# untitled.net
KiCad netlist of a schematic drawn in EAGLE
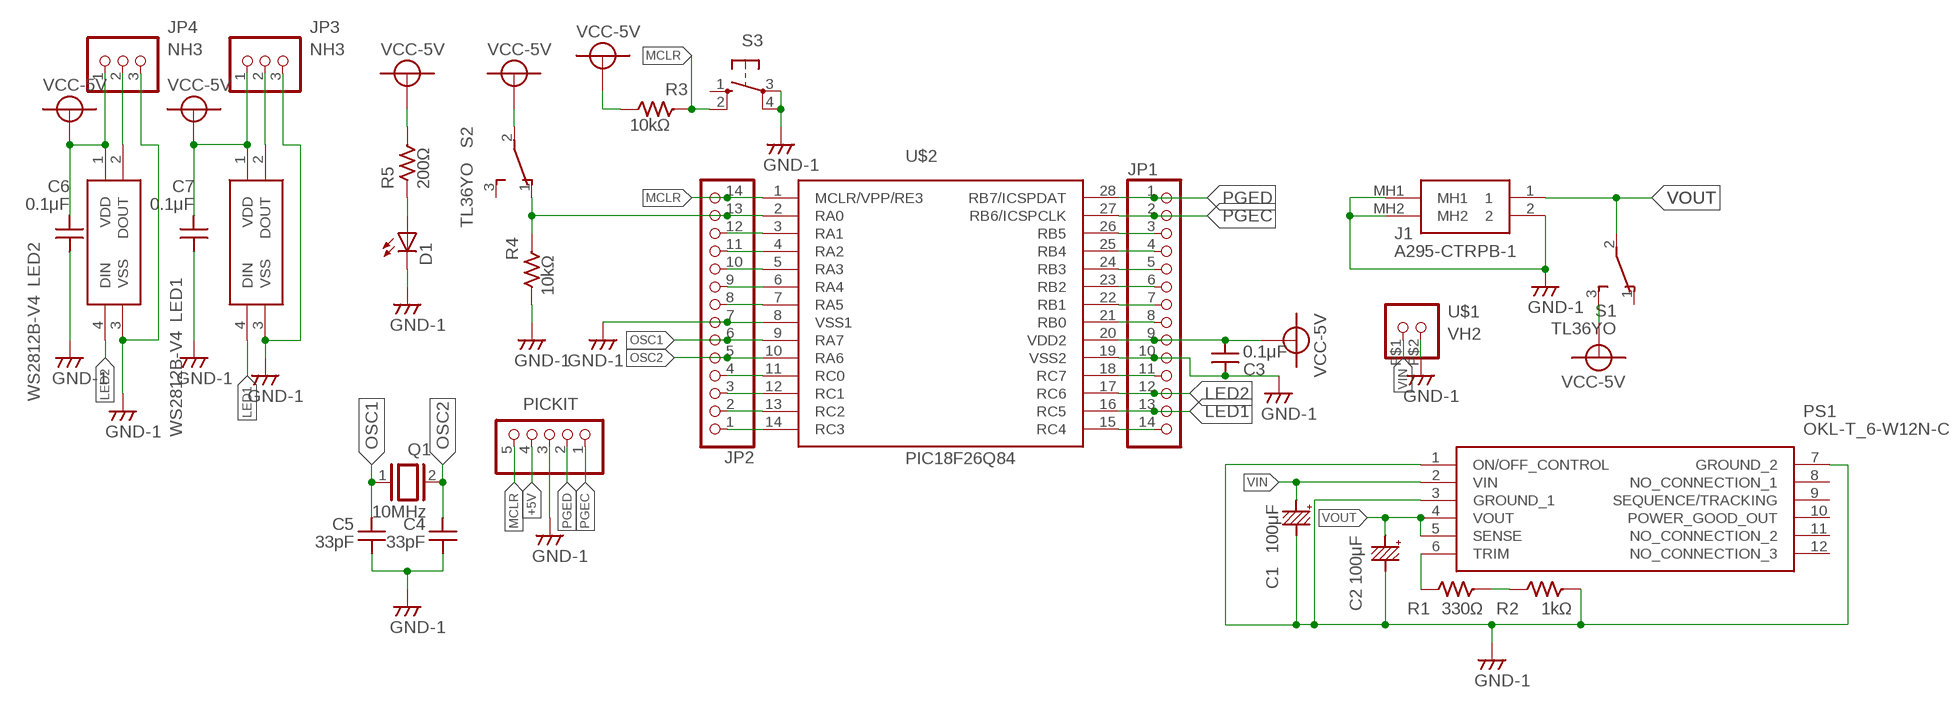
[diagram p0: schematic, sheet 1]

(export (version "E")
  (design (tool "Eeschema 10.0.6"))
  (components
    (comp (ref "C1")
      (value "100μF")
      (footprint "eagle-import:CC_3")
      (libsource (lib "eagle-import") (part "C+25V100"))
    )
    (comp (ref "C2")
      (value "100μF")
      (footprint "eagle-import:CC_3")
      (libsource (lib "eagle-import") (part "C+25V100"))
    )
    (comp (ref "C3")
      (value "0.1μF")
      (footprint "eagle-import:C_1")
      (libsource (lib "eagle-import") (part "CC2.54"))
    )
    (comp (ref "C4")
      (value "33pF")
      (footprint "eagle-import:C_1")
      (libsource (lib "eagle-import") (part "CC2.54"))
    )
    (comp (ref "C5")
      (value "33pF")
      (footprint "eagle-import:C_1")
      (libsource (lib "eagle-import") (part "CC2.54"))
    )
    (comp (ref "C6")
      (value "0.1μF")
      (footprint "eagle-import:C1608")
      (libsource (lib "eagle-import") (part "CC1068"))
    )
    (comp (ref "C7")
      (value "0.1μF")
      (footprint "eagle-import:C1608")
      (libsource (lib "eagle-import") (part "CC1068"))
    )
    (comp (ref "D1")
      (value "LED\"\"\"\"")
      (footprint "eagle-import:CHIPLED_0603")
      (libsource (lib "eagle-import") (part "LED{dblquote}{dblquote}{dblquote}{dblquote}"))
    )
    (comp (ref "J1")
      (value "A295-CTRPB-1")
      (footprint "eagle-import:A295CTRPB1")
      (libsource (lib "eagle-import") (part "A295-CTRPB-1"))
    )
    (comp (ref "JP1")
      (value "PINHD-1X14")
      (footprint "eagle-import:1X14")
      (libsource (lib "eagle-import") (part "PINHD-1X14"))
    )
    (comp (ref "JP2")
      (value "PINHD-1X14")
      (footprint "eagle-import:1X14")
      (libsource (lib "eagle-import") (part "PINHD-1X14"))
    )
    (comp (ref "JP3")
      (value "NH3")
      (footprint "eagle-import:NH3")
      (libsource (lib "eagle-import") (part "NH3"))
    )
    (comp (ref "JP4")
      (value "NH3")
      (footprint "eagle-import:NH3")
      (libsource (lib "eagle-import") (part "NH3"))
    )
    (comp (ref "LED1")
      (value "WS2812B-V4")
      (footprint "eagle-import:WS2812BV4")
      (libsource (lib "eagle-import") (part "WS2812B-V4"))
    )
    (comp (ref "LED2")
      (value "WS2812B-V4")
      (footprint "eagle-import:WS2812BV4")
      (libsource (lib "eagle-import") (part "WS2812B-V4"))
    )
    (comp (ref "PICKIT")
      (value "PINHD-1X5/90")
      (footprint "eagle-import:1X05_90")
      (libsource (lib "eagle-import") (part "PINHD-1X5/90"))
    )
    (comp (ref "PS1")
      (value "OKL-T_6-W12N-C")
      (footprint "eagle-import:OKLT6W12NC")
      (fields
        (field (name "ARROW_PART_NUMBER") "OKL-T/6-W12N-C")
        (field (name "MOUSER_PART_NUMBER") "580-OKL-T/6-W12N-C")
      )
      (libsource (lib "eagle-import") (part "OKL-T_6-W12N-C"))
    )
    (comp (ref "Q1")
      (value "10MHz")
      (footprint "eagle-import:QS")
      (libsource (lib "eagle-import") (part "XTAL/S"))
    )
    (comp (ref "R1")
      (value "330Ω")
      (footprint "eagle-import:C3216")
      (libsource (lib "eagle-import") (part "R3216(1206)"))
    )
    (comp (ref "R2")
      (value "1kΩ")
      (footprint "eagle-import:2012")
      (libsource (lib "eagle-import") (part "R2012"))
    )
    (comp (ref "R3")
      (value "10kΩ")
      (footprint "eagle-import:2012")
      (libsource (lib "eagle-import") (part "R2012"))
    )
    (comp (ref "R4")
      (value "10kΩ")
      (footprint "eagle-import:2012")
      (libsource (lib "eagle-import") (part "R2012"))
    )
    (comp (ref "R5")
      (value "200Ω")
      (footprint "eagle-import:C3216")
      (libsource (lib "eagle-import") (part "R3216(1206)"))
    )
    (comp (ref "S1")
      (value "TL36YO")
      (footprint "eagle-import:TL3XYO")
      (libsource (lib "eagle-import") (part "TL36YO"))
    )
    (comp (ref "S2")
      (value "TL36YO")
      (footprint "eagle-import:TL3XYO")
      (libsource (lib "eagle-import") (part "TL36YO"))
    )
    (comp (ref "S3")
      (value "10-XX")
      (footprint "eagle-import:B3F-10XX")
      (fields (field (name "MPN") "B3F-1000"))
      (libsource (lib "eagle-import") (part "10-XX"))
    )
    (comp (ref "U$1")
      (value "VH2")
      (footprint "eagle-import:VH2")
      (libsource (lib "eagle-import") (part "VH2"))
    )
    (comp (ref "U$2")
      (value "PIC18F26Q84")
      (footprint "eagle-import:DIL28-3")
      (libsource (lib "eagle-import") (part "PIC18F26Q84"))
    )
  )
  (nets
    (net (code "1") (name "+5V") (class "Default")
      (node (ref "C3") (pin "P$1") (pinfunction "P$1_P$1") (pintype "passive"))
      (node (ref "C6") (pin "2") (pinfunction "P$2_2") (pintype "passive"))
      (node (ref "C7") (pin "2") (pinfunction "P$2_2") (pintype "passive"))
      (node (ref "JP1") (pin "9") (pinfunction "9_9") (pintype "passive"))
      (node (ref "JP3") (pin "1") (pinfunction "P$1_1") (pintype "bidirectional"))
      (node (ref "JP4") (pin "1") (pinfunction "P$1_1") (pintype "bidirectional"))
      (node (ref "LED1") (pin "1") (pinfunction "VDD_1") (pintype "bidirectional"))
      (node (ref "LED2") (pin "1") (pinfunction "VDD_1") (pintype "bidirectional"))
      (node (ref "PICKIT") (pin "4") (pinfunction "4_4") (pintype "passive"))
      (node (ref "R3") (pin "1") (pinfunction "P$1_1") (pintype "passive"))
      (node (ref "R5") (pin "2") (pinfunction "P$2_2") (pintype "passive"))
      (node (ref "S1") (pin "3") (pinfunction "S_3") (pintype "passive"))
      (node (ref "S2") (pin "2") (pinfunction "P_2") (pintype "passive"))
      (node (ref "U$2") (pin "20") (pinfunction "VDD2_20") (pintype "bidirectional"))
    )
    (net (code "2") (name "GND-1") (class "Default")
      (node (ref "C1") (pin "-") (pinfunction "P$2-_-") (pintype "passive"))
      (node (ref "C2") (pin "-") (pinfunction "P$2-_-") (pintype "passive"))
      (node (ref "C3") (pin "P$2") (pinfunction "P$2_P$2") (pintype "passive"))
      (node (ref "C4") (pin "P$1") (pinfunction "P$1_P$1") (pintype "passive"))
      (node (ref "C5") (pin "P$1") (pinfunction "P$1_P$1") (pintype "passive"))
      (node (ref "C6") (pin "1") (pinfunction "P$1_1") (pintype "passive"))
      (node (ref "C7") (pin "1") (pinfunction "P$1_1") (pintype "passive"))
      (node (ref "D1") (pin "C") (pinfunction "C_C") (pintype "passive"))
      (node (ref "J1") (pin "2") (pinfunction "2_2") (pintype "bidirectional"))
      (node (ref "J1") (pin "MH1") (pinfunction "MH1_MH1") (pintype "bidirectional"))
      (node (ref "J1") (pin "MH2") (pinfunction "MH2_MH2") (pintype "bidirectional"))
      (node (ref "JP1") (pin "10") (pinfunction "10_10") (pintype "passive"))
      (node (ref "JP2") (pin "7") (pinfunction "7_7") (pintype "passive"))
      (node (ref "JP3") (pin "3") (pinfunction "P$3_3") (pintype "bidirectional"))
      (node (ref "JP4") (pin "3") (pinfunction "P$3_3") (pintype "bidirectional"))
      (node (ref "LED1") (pin "3") (pinfunction "VSS_3") (pintype "bidirectional"))
      (node (ref "LED2") (pin "3") (pinfunction "VSS_3") (pintype "bidirectional"))
      (node (ref "PICKIT") (pin "3") (pinfunction "3_3") (pintype "passive"))
      (node (ref "PS1") (pin "1") (pinfunction "ON/OFF_CONTROL_1") (pintype "bidirectional"))
      (node (ref "PS1") (pin "3") (pinfunction "GROUND_1_3") (pintype "bidirectional"))
      (node (ref "PS1") (pin "7") (pinfunction "GROUND_2_7") (pintype "bidirectional"))
      (node (ref "R2") (pin "2") (pinfunction "P$2_2") (pintype "passive"))
      (node (ref "R4") (pin "1") (pinfunction "P$1_1") (pintype "passive"))
      (node (ref "S3") (pin "3") (pinfunction "P_3") (pintype "passive"))
      (node (ref "S3") (pin "4") (pinfunction "P1_4") (pintype "passive"))
      (node (ref "U$1") (pin "P$2") (pinfunction "P$2_P$2") (pintype "bidirectional"))
      (node (ref "U$2") (pin "19") (pinfunction "VSS2_19") (pintype "bidirectional"))
      (node (ref "U$2") (pin "8") (pinfunction "VSS1_8") (pintype "bidirectional"))
    )
    (net (code "3") (name "LED1") (class "Default")
      (node (ref "JP1") (pin "13") (pinfunction "13_13") (pintype "passive"))
      (node (ref "LED1") (pin "4") (pinfunction "DIN_4") (pintype "bidirectional"))
      (node (ref "U$2") (pin "16") (pinfunction "RC5_16") (pintype "bidirectional"))
    )
    (net (code "4") (name "LED2") (class "Default")
      (node (ref "JP1") (pin "12") (pinfunction "12_12") (pintype "passive"))
      (node (ref "LED2") (pin "4") (pinfunction "DIN_4") (pintype "bidirectional"))
      (node (ref "U$2") (pin "17") (pinfunction "RC6_17") (pintype "bidirectional"))
    )
    (net (code "5") (name "MCLR") (class "Default")
      (node (ref "JP2") (pin "14") (pinfunction "14_14") (pintype "passive"))
      (node (ref "PICKIT") (pin "5") (pinfunction "5_5") (pintype "passive"))
      (node (ref "R3") (pin "2") (pinfunction "P$2_2") (pintype "passive"))
      (node (ref "S3") (pin "2") (pinfunction "S1_2") (pintype "passive"))
      (node (ref "U$2") (pin "1") (pinfunction "MCLR/VPP/RE3_1") (pintype "bidirectional"))
    )
    (net (code "6") (name "Net-(JP3-P$2)") (class "Default")
      (node (ref "JP3") (pin "2") (pinfunction "P$2_2") (pintype "bidirectional"))
      (node (ref "LED1") (pin "2") (pinfunction "DOUT_2") (pintype "bidirectional"))
    )
    (net (code "7") (name "Net-(JP4-P$2)") (class "Default")
      (node (ref "JP4") (pin "2") (pinfunction "P$2_2") (pintype "bidirectional"))
      (node (ref "LED2") (pin "2") (pinfunction "DOUT_2") (pintype "bidirectional"))
    )
    (net (code "8") (name "Net-(PS1-TRIM)") (class "Default")
      (node (ref "PS1") (pin "6") (pinfunction "TRIM_6") (pintype "bidirectional"))
      (node (ref "R1") (pin "1") (pinfunction "P$1_1") (pintype "passive"))
    )
    (net (code "9") (name "Net-(R1-P$2)") (class "Default")
      (node (ref "R1") (pin "2") (pinfunction "P$2_2") (pintype "passive"))
      (node (ref "R2") (pin "1") (pinfunction "P$1_1") (pintype "passive"))
    )
    (net (code "10") (name "Net-(R4-P$2)") (class "Default")
      (node (ref "JP2") (pin "13") (pinfunction "13_13") (pintype "passive"))
      (node (ref "R4") (pin "2") (pinfunction "P$2_2") (pintype "passive"))
      (node (ref "S2") (pin "1") (pinfunction "O_1") (pintype "passive"))
      (node (ref "U$2") (pin "2") (pinfunction "RA0_2") (pintype "bidirectional"))
    )
    (net (code "11") (name "Net-(R5-P$1)") (class "Default")
      (node (ref "D1") (pin "A") (pinfunction "A_A") (pintype "passive"))
      (node (ref "R5") (pin "1") (pinfunction "P$1_1") (pintype "passive"))
    )
    (net (code "12") (name "Net-(U$2-RA1)") (class "Default")
      (node (ref "JP2") (pin "12") (pinfunction "12_12") (pintype "passive"))
      (node (ref "U$2") (pin "3") (pinfunction "RA1_3") (pintype "bidirectional"))
    )
    (net (code "13") (name "Net-(U$2-RA2)") (class "Default")
      (node (ref "JP2") (pin "11") (pinfunction "11_11") (pintype "passive"))
      (node (ref "U$2") (pin "4") (pinfunction "RA2_4") (pintype "bidirectional"))
    )
    (net (code "14") (name "Net-(U$2-RA3)") (class "Default")
      (node (ref "JP2") (pin "10") (pinfunction "10_10") (pintype "passive"))
      (node (ref "U$2") (pin "5") (pinfunction "RA3_5") (pintype "bidirectional"))
    )
    (net (code "15") (name "Net-(U$2-RA4)") (class "Default")
      (node (ref "JP2") (pin "9") (pinfunction "9_9") (pintype "passive"))
      (node (ref "U$2") (pin "6") (pinfunction "RA4_6") (pintype "bidirectional"))
    )
    (net (code "16") (name "Net-(U$2-RA5)") (class "Default")
      (node (ref "JP2") (pin "8") (pinfunction "8_8") (pintype "passive"))
      (node (ref "U$2") (pin "7") (pinfunction "RA5_7") (pintype "bidirectional"))
    )
    (net (code "17") (name "Net-(U$2-RB0)") (class "Default")
      (node (ref "JP1") (pin "8") (pinfunction "8_8") (pintype "passive"))
      (node (ref "U$2") (pin "21") (pinfunction "RB0_21") (pintype "bidirectional"))
    )
    (net (code "18") (name "Net-(U$2-RB1)") (class "Default")
      (node (ref "JP1") (pin "7") (pinfunction "7_7") (pintype "passive"))
      (node (ref "U$2") (pin "22") (pinfunction "RB1_22") (pintype "bidirectional"))
    )
    (net (code "19") (name "Net-(U$2-RB2)") (class "Default")
      (node (ref "JP1") (pin "6") (pinfunction "6_6") (pintype "passive"))
      (node (ref "U$2") (pin "23") (pinfunction "RB2_23") (pintype "bidirectional"))
    )
    (net (code "20") (name "Net-(U$2-RB3)") (class "Default")
      (node (ref "JP1") (pin "5") (pinfunction "5_5") (pintype "passive"))
      (node (ref "U$2") (pin "24") (pinfunction "RB3_24") (pintype "bidirectional"))
    )
    (net (code "21") (name "Net-(U$2-RB4)") (class "Default")
      (node (ref "JP1") (pin "4") (pinfunction "4_4") (pintype "passive"))
      (node (ref "U$2") (pin "25") (pinfunction "RB4_25") (pintype "bidirectional"))
    )
    (net (code "22") (name "Net-(U$2-RB5)") (class "Default")
      (node (ref "JP1") (pin "3") (pinfunction "3_3") (pintype "passive"))
      (node (ref "U$2") (pin "26") (pinfunction "RB5_26") (pintype "bidirectional"))
    )
    (net (code "23") (name "Net-(U$2-RC0)") (class "Default")
      (node (ref "JP2") (pin "4") (pinfunction "4_4") (pintype "passive"))
      (node (ref "U$2") (pin "11") (pinfunction "RC0_11") (pintype "bidirectional"))
    )
    (net (code "24") (name "Net-(U$2-RC1)") (class "Default")
      (node (ref "JP2") (pin "3") (pinfunction "3_3") (pintype "passive"))
      (node (ref "U$2") (pin "12") (pinfunction "RC1_12") (pintype "bidirectional"))
    )
    (net (code "25") (name "Net-(U$2-RC2)") (class "Default")
      (node (ref "JP2") (pin "2") (pinfunction "2_2") (pintype "passive"))
      (node (ref "U$2") (pin "13") (pinfunction "RC2_13") (pintype "bidirectional"))
    )
    (net (code "26") (name "Net-(U$2-RC3)") (class "Default")
      (node (ref "JP2") (pin "1") (pinfunction "1_1") (pintype "passive"))
      (node (ref "U$2") (pin "14") (pinfunction "RC3_14") (pintype "bidirectional"))
    )
    (net (code "27") (name "Net-(U$2-RC4)") (class "Default")
      (node (ref "JP1") (pin "14") (pinfunction "14_14") (pintype "passive"))
      (node (ref "U$2") (pin "15") (pinfunction "RC4_15") (pintype "bidirectional"))
    )
    (net (code "28") (name "Net-(U$2-RC7)") (class "Default")
      (node (ref "JP1") (pin "11") (pinfunction "11_11") (pintype "passive"))
      (node (ref "U$2") (pin "18") (pinfunction "RC7_18") (pintype "bidirectional"))
    )
    (net (code "29") (name "OSC1") (class "Default")
      (node (ref "C5") (pin "P$2") (pinfunction "P$2_P$2") (pintype "passive"))
      (node (ref "JP2") (pin "6") (pinfunction "6_6") (pintype "passive"))
      (node (ref "Q1") (pin "1") (pinfunction "1_1") (pintype "passive"))
      (node (ref "U$2") (pin "9") (pinfunction "RA7_9") (pintype "bidirectional"))
    )
    (net (code "30") (name "OSC2") (class "Default")
      (node (ref "C4") (pin "P$2") (pinfunction "P$2_P$2") (pintype "passive"))
      (node (ref "JP2") (pin "5") (pinfunction "5_5") (pintype "passive"))
      (node (ref "Q1") (pin "2") (pinfunction "2_2") (pintype "passive"))
      (node (ref "U$2") (pin "10") (pinfunction "RA6_10") (pintype "bidirectional"))
    )
    (net (code "31") (name "PGEC") (class "Default")
      (node (ref "JP1") (pin "2") (pinfunction "2_2") (pintype "passive"))
      (node (ref "PICKIT") (pin "1") (pinfunction "1_1") (pintype "passive"))
      (node (ref "U$2") (pin "27") (pinfunction "RB6/ICSPCLK_27") (pintype "bidirectional"))
    )
    (net (code "32") (name "PGED") (class "Default")
      (node (ref "JP1") (pin "1") (pinfunction "1_1") (pintype "passive"))
      (node (ref "PICKIT") (pin "2") (pinfunction "2_2") (pintype "passive"))
      (node (ref "U$2") (pin "28") (pinfunction "RB7/ICSPDAT_28") (pintype "bidirectional"))
    )
    (net (code "33") (name "VIN") (class "Default")
      (node (ref "C1") (pin "+") (pinfunction "P$1+_+") (pintype "passive"))
      (node (ref "PS1") (pin "2") (pinfunction "VIN_2") (pintype "bidirectional"))
      (node (ref "U$1") (pin "P$1") (pinfunction "P$1_P$1") (pintype "bidirectional"))
    )
    (net (code "34") (name "VOUT") (class "Default")
      (node (ref "C2") (pin "+") (pinfunction "P$1+_+") (pintype "passive"))
      (node (ref "J1") (pin "1") (pinfunction "1_1") (pintype "bidirectional"))
      (node (ref "PS1") (pin "4") (pinfunction "VOUT_4") (pintype "bidirectional"))
      (node (ref "PS1") (pin "5") (pinfunction "SENSE_5") (pintype "bidirectional"))
      (node (ref "S1") (pin "2") (pinfunction "P_2") (pintype "passive"))
    )
    (net (code "35") (name "unconnected-(PS1-NO_CONNECTION_1-Pad8)") (class "Default")
      (node (ref "PS1") (pin "8") (pinfunction "NO_CONNECTION_1_8") (pintype "bidirectional"))
    )
    (net (code "36") (name "unconnected-(PS1-NO_CONNECTION_2-Pad11)") (class "Default")
      (node (ref "PS1") (pin "11") (pinfunction "NO_CONNECTION_2_11") (pintype "bidirectional"))
    )
    (net (code "37") (name "unconnected-(PS1-NO_CONNECTION_3-Pad12)") (class "Default")
      (node (ref "PS1") (pin "12") (pinfunction "NO_CONNECTION_3_12") (pintype "bidirectional"))
    )
    (net (code "38") (name "unconnected-(PS1-POWER_GOOD_OUT-Pad10)") (class "Default")
      (node (ref "PS1") (pin "10") (pinfunction "POWER_GOOD_OUT_10") (pintype "bidirectional"))
    )
    (net (code "39") (name "unconnected-(PS1-SEQUENCE{slash}TRACKING-Pad9)") (class "Default")
      (node (ref "PS1") (pin "9") (pinfunction "SEQUENCE/TRACKING_9") (pintype "bidirectional"))
    )
    (net (code "40") (name "unconnected-(S1-O-Pad1)") (class "Default")
      (node (ref "S1") (pin "1") (pinfunction "O_1") (pintype "passive"))
    )
    (net (code "41") (name "unconnected-(S2-S-Pad3)") (class "Default")
      (node (ref "S2") (pin "3") (pinfunction "S_3") (pintype "passive"))
    )
    (net (code "42") (name "unconnected-(S3-S-Pad1)") (class "Default")
      (node (ref "S3") (pin "1") (pinfunction "S_1") (pintype "passive"))
    )
  )
)
